# VehicleBattVMonIoT_SMD.net
KiCad netlist of a schematic drawn in EAGLE
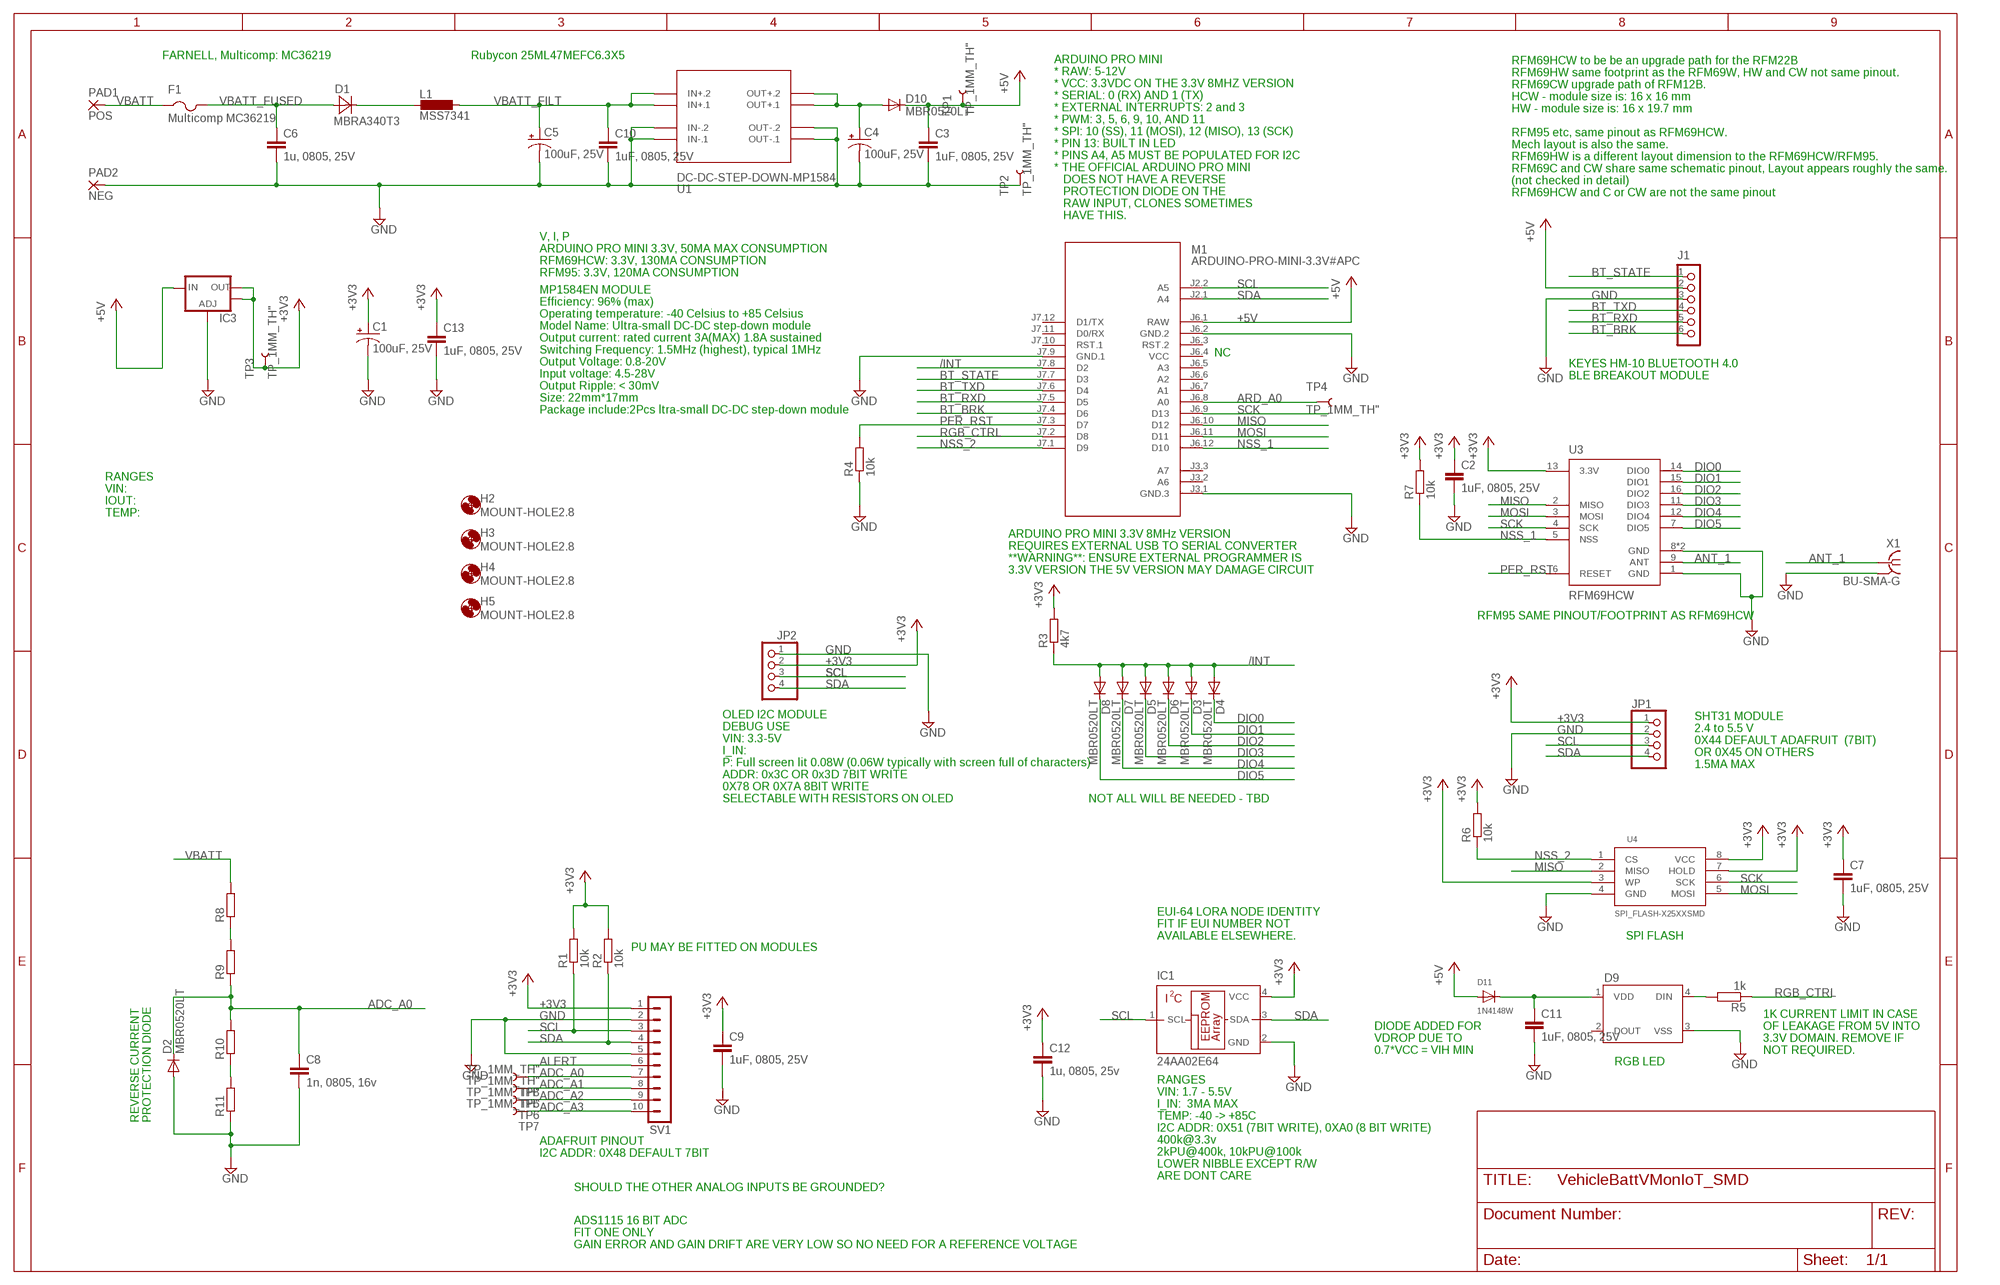
[diagram p0: schematic, sheet 1]

(export (version "E")
  (design (tool "Eeschema 10.0.6"))
  (components
    (comp (ref "C1")
      (value "100uF, 25V")
      (footprint "eagle-import:CPOL-RADIAL-100UF-25V")
      (libsource (lib "eagle-import") (part "CAP_POLPTH1"))
    )
    (comp (ref "C2")
      (value "1uF, 0805, 25V")
      (footprint "eagle-import:C0805")
      (libsource (lib "eagle-import") (part "C-EUC0805"))
    )
    (comp (ref "C3")
      (value "1uF, 0805, 25V")
      (footprint "eagle-import:C0805")
      (libsource (lib "eagle-import") (part "C-EUC0805"))
    )
    (comp (ref "C4")
      (value "100uF, 25V")
      (footprint "eagle-import:CPOL-RADIAL-100UF-25V")
      (libsource (lib "eagle-import") (part "CAP_POLPTH1"))
    )
    (comp (ref "C5")
      (value "100uF, 25V")
      (footprint "eagle-import:CPOL-RADIAL-100UF-25V")
      (libsource (lib "eagle-import") (part "CAP_POLPTH1"))
    )
    (comp (ref "C6")
      (value "1u, 0805, 25V")
      (footprint "eagle-import:C0805")
      (libsource (lib "eagle-import") (part "C-EUC0805"))
    )
    (comp (ref "C7")
      (value "1uF, 0805, 25V")
      (footprint "eagle-import:C0805")
      (libsource (lib "eagle-import") (part "C-EUC0805"))
    )
    (comp (ref "C8")
      (value "1n, 0805, 16v")
      (footprint "eagle-import:C0805")
      (libsource (lib "eagle-import") (part "C-EUC0805"))
    )
    (comp (ref "C9")
      (value "1uF, 0805, 25V")
      (footprint "eagle-import:C0805")
      (libsource (lib "eagle-import") (part "C-EUC0805"))
    )
    (comp (ref "C10")
      (value "1uF, 0805, 25V")
      (footprint "eagle-import:C0805")
      (libsource (lib "eagle-import") (part "C-EUC0805"))
    )
    (comp (ref "C11")
      (value "1uF, 0805, 25V")
      (footprint "eagle-import:C0805")
      (libsource (lib "eagle-import") (part "C-EUC0805"))
    )
    (comp (ref "C12")
      (value "1u, 0805, 25v")
      (footprint "eagle-import:C0805")
      (libsource (lib "eagle-import") (part "C-EUC0805"))
    )
    (comp (ref "C13")
      (value "1uF, 0805, 25V")
      (footprint "eagle-import:C0805")
      (libsource (lib "eagle-import") (part "C-EUC0805"))
    )
    (comp (ref "D1")
      (value "MBRA340T3")
      (footprint "eagle-import:SMA")
      (libsource (lib "eagle-import") (part "MBRA340T3"))
    )
    (comp (ref "D2")
      (value "MBR0520LT")
      (footprint "eagle-import:SOD123")
      (libsource (lib "eagle-import") (part "MBR0520LT"))
    )
    (comp (ref "D3")
      (value "MBR0520LT")
      (footprint "eagle-import:SOD123")
      (libsource (lib "eagle-import") (part "MBR0520LT"))
    )
    (comp (ref "D4")
      (value "MBR0520LT")
      (footprint "eagle-import:SOD123")
      (libsource (lib "eagle-import") (part "MBR0520LT"))
    )
    (comp (ref "D5")
      (value "MBR0520LT")
      (footprint "eagle-import:SOD123")
      (libsource (lib "eagle-import") (part "MBR0520LT"))
    )
    (comp (ref "D6")
      (value "MBR0520LT")
      (footprint "eagle-import:SOD123")
      (libsource (lib "eagle-import") (part "MBR0520LT"))
    )
    (comp (ref "D7")
      (value "MBR0520LT")
      (footprint "eagle-import:SOD123")
      (libsource (lib "eagle-import") (part "MBR0520LT"))
    )
    (comp (ref "D8")
      (value "MBR0520LT")
      (footprint "eagle-import:SOD123")
      (libsource (lib "eagle-import") (part "MBR0520LT"))
    )
    (comp (ref "D9")
      (value "WS2812B")
      (footprint "eagle-import:WS2812B")
      (libsource (lib "eagle-import") (part "WS2812B"))
    )
    (comp (ref "D10")
      (value "MBR0520LT")
      (footprint "eagle-import:SOD123")
      (libsource (lib "eagle-import") (part "MBR0520LT"))
    )
    (comp (ref "D11")
      (value "1N4148W")
      (footprint "eagle-import:SOD-323F")
      (libsource (lib "eagle-import") (part "DIODESOD-323F"))
    )
    (comp (ref "F1")
      (value "Multicomp MC36219")
      (footprint "eagle-import:1812")
      (libsource (lib "eagle-import") (part "PTCFUSE-1812"))
    )
    (comp (ref "H2")
      (value "MOUNT-HOLE2.8")
      (footprint "eagle-import:2,8")
      (libsource (lib "eagle-import") (part "MOUNT-HOLE2.8"))
    )
    (comp (ref "H3")
      (value "MOUNT-HOLE2.8")
      (footprint "eagle-import:2,8")
      (libsource (lib "eagle-import") (part "MOUNT-HOLE2.8"))
    )
    (comp (ref "H4")
      (value "MOUNT-HOLE2.8")
      (footprint "eagle-import:2,8")
      (libsource (lib "eagle-import") (part "MOUNT-HOLE2.8"))
    )
    (comp (ref "H5")
      (value "MOUNT-HOLE2.8")
      (footprint "eagle-import:2,8")
      (libsource (lib "eagle-import") (part "MOUNT-HOLE2.8"))
    )
    (comp (ref "IC1")
      (value "24AA02E64")
      (footprint "eagle-import:SOT23-5L")
      (fields (field (name "MF") "MICROCHIP") (field (name "MPN") "24AA00T-I/OTG"))
      (libsource (lib "eagle-import") (part "2400OTAA"))
    )
    (comp (ref "IC3")
      (value "V_REG_LM1117SOT223")
      (footprint "eagle-import:SOT223")
      (libsource (lib "eagle-import") (part "V_REG_LM1117SOT223"))
    )
    (comp (ref "J1")
      (value "CON_HEADER_1X06-SMD-RIGHT-ANGLED")
      (footprint "eagle-import:M1X6_MALE_RIGHT_ANGLED_SMD")
      (libsource (lib "eagle-import") (part "CON_HEADER_1X06-SMD-RIGHT-ANGLED"))
    )
    (comp (ref "JP1")
      (value "PINHD-1X4")
      (footprint "eagle-import:1X04")
      (libsource (lib "eagle-import") (part "PINHD-1X4"))
    )
    (comp (ref "JP2")
      (value "PINHD-1X4")
      (footprint "eagle-import:1X04")
      (libsource (lib "eagle-import") (part "PINHD-1X4"))
    )
    (comp (ref "L1")
      (value "MSS7341")
      (footprint "eagle-import:MSS7341")
      (libsource (lib "eagle-import") (part "MSS7341"))
    )
    (comp (ref "M1")
      (value "ARDUINO-PRO-MINI-3.3V#APC")
      (footprint "eagle-import:ARDUINO-PRO-MINI#APC")
      (libsource (lib "eagle-import") (part "ARDUINO-PRO-MINI-#APC3.3V"))
    )
    (comp (ref "PAD1")
      (value "POS")
      (footprint "eagle-import:3,81_1,4")
      (libsource (lib "eagle-import") (part "3,81/1,4"))
    )
    (comp (ref "PAD2")
      (value "NEG")
      (footprint "eagle-import:3,81_1,4")
      (libsource (lib "eagle-import") (part "3,81/1,4"))
    )
    (comp (ref "R1")
      (value "10k")
      (footprint "eagle-import:R0805")
      (libsource (lib "eagle-import") (part "R-EU_R0805"))
    )
    (comp (ref "R2")
      (value "10k")
      (footprint "eagle-import:R0805")
      (libsource (lib "eagle-import") (part "R-EU_R0805"))
    )
    (comp (ref "R3")
      (value "4k7")
      (footprint "eagle-import:R0805")
      (libsource (lib "eagle-import") (part "R-EU_R0805"))
    )
    (comp (ref "R4")
      (value "10k")
      (footprint "eagle-import:R0805")
      (libsource (lib "eagle-import") (part "R-EU_R0805"))
    )
    (comp (ref "R5")
      (value "1k")
      (footprint "eagle-import:R0805")
      (libsource (lib "eagle-import") (part "R-EU_R0805"))
    )
    (comp (ref "R6")
      (value "10k")
      (footprint "eagle-import:R0805")
      (libsource (lib "eagle-import") (part "R-EU_R0805"))
    )
    (comp (ref "R7")
      (value "10k")
      (footprint "eagle-import:R0805")
      (libsource (lib "eagle-import") (part "R-EU_R0805"))
    )
    (comp (ref "R8")
      (value "R-EU_R0805")
      (footprint "eagle-import:R0805")
      (libsource (lib "eagle-import") (part "R-EU_R0805"))
    )
    (comp (ref "R9")
      (value "R-EU_R0805")
      (footprint "eagle-import:R0805")
      (libsource (lib "eagle-import") (part "R-EU_R0805"))
    )
    (comp (ref "R10")
      (value "R-EU_R0805")
      (footprint "eagle-import:R0805")
      (libsource (lib "eagle-import") (part "R-EU_R0805"))
    )
    (comp (ref "R11")
      (value "R-EU_R0805")
      (footprint "eagle-import:R0805")
      (libsource (lib "eagle-import") (part "R-EU_R0805"))
    )
    (comp (ref "SV1")
      (value "MA10-1W")
      (footprint "eagle-import:MA10-1W")
      (libsource (lib "eagle-import") (part "MA10-1W"))
    )
    (comp (ref "TP1")
      (value "TP_1MM_TH\"")
      (footprint "eagle-import:TP_1MM_TH")
      (libsource (lib "eagle-import") (part "TP_1MM_TH{dblquote}"))
    )
    (comp (ref "TP2")
      (value "TP_1MM_TH\"")
      (footprint "eagle-import:TP_1MM_TH")
      (libsource (lib "eagle-import") (part "TP_1MM_TH{dblquote}"))
    )
    (comp (ref "TP3")
      (value "TP_1MM_TH\"")
      (footprint "eagle-import:TP_1MM_TH")
      (libsource (lib "eagle-import") (part "TP_1MM_TH{dblquote}"))
    )
    (comp (ref "TP4")
      (value "TP_1MM_TH\"")
      (footprint "eagle-import:TP_1MM_TH")
      (libsource (lib "eagle-import") (part "TP_1MM_TH{dblquote}"))
    )
    (comp (ref "TP5")
      (value "TP_1MM_TH\"")
      (footprint "eagle-import:TP_1MM_TH")
      (libsource (lib "eagle-import") (part "TP_1MM_TH{dblquote}"))
    )
    (comp (ref "TP6")
      (value "TP_1MM_TH\"")
      (footprint "eagle-import:TP_1MM_TH")
      (libsource (lib "eagle-import") (part "TP_1MM_TH{dblquote}"))
    )
    (comp (ref "TP7")
      (value "TP_1MM_TH\"")
      (footprint "eagle-import:TP_1MM_TH")
      (libsource (lib "eagle-import") (part "TP_1MM_TH{dblquote}"))
    )
    (comp (ref "TP8")
      (value "TP_1MM_TH\"")
      (footprint "eagle-import:TP_1MM_TH")
      (libsource (lib "eagle-import") (part "TP_1MM_TH{dblquote}"))
    )
    (comp (ref "U1")
      (value "DC-DC-STEP-DOWN-MP1584")
      (footprint "eagle-import:DC-DC-STEP-DOWN-MP1584")
      (libsource (lib "eagle-import") (part "DC-DC-STEP-DOWN-MP1584"))
    )
    (comp (ref "U3")
      (value "RFM69HCW")
      (footprint "eagle-import:RFM69HCW-XXXS2")
      (libsource (lib "eagle-import") (part "RFM69HCW"))
    )
    (comp (ref "U4")
      (value "SPI_FLASH-X25XXSMD")
      (footprint "eagle-import:SO08")
      (libsource (lib "eagle-import") (part "SPI_FLASH-X25XXSMD"))
    )
    (comp (ref "X1")
      (value "BU-SMA-G")
      (footprint "eagle-import:BU-SMA-G")
      (libsource (lib "eagle-import") (part "BU-SMA-G"))
    )
  )
  (nets
    (net (code "1") (name "+3V3") (class "Default")
      (node (ref "C1") (pin "1") (pinfunction "+_1") (pintype "passive"))
      (node (ref "C12") (pin "1") (pinfunction "1_1") (pintype "passive"))
      (node (ref "C13") (pin "1") (pinfunction "1_1") (pintype "passive"))
      (node (ref "C2") (pin "1") (pinfunction "1_1") (pintype "passive"))
      (node (ref "C7") (pin "1") (pinfunction "1_1") (pintype "passive"))
      (node (ref "C9") (pin "1") (pinfunction "1_1") (pintype "passive"))
      (node (ref "IC1") (pin "4") (pinfunction "VCC_4") (pintype "power_in"))
      (node (ref "IC3") (pin "2") (pinfunction "OUT_2") (pintype "output"))
      (node (ref "IC3") (pin "4") (pinfunction "OUT_4") (pintype "output"))
      (node (ref "JP1") (pin "1") (pinfunction "1_1") (pintype "passive"))
      (node (ref "JP2") (pin "2") (pinfunction "2_2") (pintype "passive"))
      (node (ref "R1") (pin "2") (pinfunction "2_2") (pintype "passive"))
      (node (ref "R2") (pin "2") (pinfunction "2_2") (pintype "passive"))
      (node (ref "R3") (pin "2") (pinfunction "2_2") (pintype "passive"))
      (node (ref "R6") (pin "2") (pinfunction "2_2") (pintype "passive"))
      (node (ref "R7") (pin "2") (pinfunction "2_2") (pintype "passive"))
      (node (ref "SV1") (pin "1") (pinfunction "1_1") (pintype "passive"))
      (node (ref "TP3") (pin "P$1") (pinfunction "1_P$1") (pintype "bidirectional"))
      (node (ref "U3") (pin "13") (pinfunction "3.3V_13") (pintype "power_in"))
      (node (ref "U4") (pin "3") (pinfunction "WP_3") (pintype "bidirectional"))
      (node (ref "U4") (pin "7") (pinfunction "HOLD_7") (pintype "bidirectional"))
      (node (ref "U4") (pin "8") (pinfunction "VCC_8") (pintype "bidirectional"))
    )
    (net (code "2") (name "+5V") (class "Default")
      (node (ref "C3") (pin "1") (pinfunction "1_1") (pintype "passive"))
      (node (ref "D10") (pin "C") (pinfunction "C_C") (pintype "passive"))
      (node (ref "D11") (pin "A") (pinfunction "A_A") (pintype "passive"))
      (node (ref "IC3") (pin "3") (pinfunction "IN_3") (pintype "input"))
      (node (ref "J1") (pin "2") (pinfunction "2_2") (pintype "bidirectional"))
      (node (ref "M1") (pin "J6.1") (pinfunction "RAW_J6.1") (pintype "power_in"))
      (node (ref "TP1") (pin "P$1") (pinfunction "1_P$1") (pintype "bidirectional"))
    )
    (net (code "3") (name "/ADC_A0") (class "Default")
      (node (ref "C8") (pin "1") (pinfunction "1_1") (pintype "passive"))
      (node (ref "D2") (pin "C") (pinfunction "C_C") (pintype "passive"))
      (node (ref "R10") (pin "2") (pinfunction "2_2") (pintype "passive"))
      (node (ref "R9") (pin "1") (pinfunction "1_1") (pintype "passive"))
      (node (ref "SV1") (pin "7") (pinfunction "7_7") (pintype "passive"))
      (node (ref "TP8") (pin "P$1") (pinfunction "1_P$1") (pintype "bidirectional"))
    )
    (net (code "4") (name "/ADC_A1") (class "Default")
      (node (ref "SV1") (pin "8") (pinfunction "8_8") (pintype "passive"))
      (node (ref "TP5") (pin "P$1") (pinfunction "1_P$1") (pintype "bidirectional"))
    )
    (net (code "5") (name "/ADC_A2") (class "Default")
      (node (ref "SV1") (pin "9") (pinfunction "9_9") (pintype "passive"))
      (node (ref "TP6") (pin "P$1") (pinfunction "1_P$1") (pintype "bidirectional"))
    )
    (net (code "6") (name "/ADC_A3") (class "Default")
      (node (ref "SV1") (pin "10") (pinfunction "10_10") (pintype "passive"))
      (node (ref "TP7") (pin "P$1") (pinfunction "1_P$1") (pintype "bidirectional"))
    )
    (net (code "7") (name "/ALERT") (class "Default")
      (node (ref "SV1") (pin "6") (pinfunction "6_6") (pintype "passive"))
    )
    (net (code "8") (name "/ANT_1") (class "Default")
      (node (ref "U3") (pin "9") (pinfunction "ANT_9") (pintype "passive"))
      (node (ref "X1") (pin "1") (pinfunction "1_1") (pintype "passive"))
    )
    (net (code "9") (name "/ARD_A0") (class "Default")
      (node (ref "M1") (pin "J6.8") (pinfunction "A0_J6.8") (pintype "bidirectional"))
      (node (ref "TP4") (pin "P$1") (pinfunction "1_P$1") (pintype "bidirectional"))
    )
    (net (code "10") (name "/BT_BRK") (class "Default")
      (node (ref "J1") (pin "6") (pinfunction "6_6") (pintype "passive"))
      (node (ref "M1") (pin "J7.4") (pinfunction "D6_J7.4") (pintype "bidirectional"))
    )
    (net (code "11") (name "/BT_RXD") (class "Default")
      (node (ref "J1") (pin "5") (pinfunction "5_5") (pintype "passive"))
      (node (ref "M1") (pin "J7.5") (pinfunction "D5_J7.5") (pintype "bidirectional"))
    )
    (net (code "12") (name "/BT_STATE") (class "Default")
      (node (ref "J1") (pin "1") (pinfunction "1_1") (pintype "bidirectional"))
      (node (ref "M1") (pin "J7.7") (pinfunction "D3_J7.7") (pintype "bidirectional"))
    )
    (net (code "13") (name "/BT_TXD") (class "Default")
      (node (ref "J1") (pin "4") (pinfunction "4_4") (pintype "passive"))
      (node (ref "M1") (pin "J7.6") (pinfunction "D4_J7.6") (pintype "bidirectional"))
    )
    (net (code "14") (name "/DIO0") (class "Default")
      (node (ref "D4") (pin "C") (pinfunction "C_C") (pintype "passive"))
      (node (ref "U3") (pin "14") (pinfunction "DIO0_14") (pintype "bidirectional"))
    )
    (net (code "15") (name "/DIO1") (class "Default")
      (node (ref "D3") (pin "C") (pinfunction "C_C") (pintype "passive"))
      (node (ref "U3") (pin "15") (pinfunction "DIO1_15") (pintype "bidirectional"))
    )
    (net (code "16") (name "/DIO2") (class "Default")
      (node (ref "D6") (pin "C") (pinfunction "C_C") (pintype "passive"))
      (node (ref "U3") (pin "16") (pinfunction "DIO2_16") (pintype "bidirectional"))
    )
    (net (code "17") (name "/DIO3") (class "Default")
      (node (ref "D5") (pin "C") (pinfunction "C_C") (pintype "passive"))
      (node (ref "U3") (pin "11") (pinfunction "DIO3_11") (pintype "bidirectional"))
    )
    (net (code "18") (name "/DIO4") (class "Default")
      (node (ref "D7") (pin "C") (pinfunction "C_C") (pintype "passive"))
      (node (ref "U3") (pin "12") (pinfunction "DIO4_12") (pintype "bidirectional"))
    )
    (net (code "19") (name "/DIO5") (class "Default")
      (node (ref "D8") (pin "C") (pinfunction "C_C") (pintype "passive"))
      (node (ref "U3") (pin "7") (pinfunction "DIO5_7") (pintype "bidirectional"))
    )
    (net (code "20") (name "/MISO") (class "Default")
      (node (ref "M1") (pin "J6.10") (pinfunction "D12_J6.10") (pintype "bidirectional"))
      (node (ref "U3") (pin "2") (pinfunction "MISO_2") (pintype "bidirectional"))
      (node (ref "U4") (pin "2") (pinfunction "MISO_2") (pintype "bidirectional"))
    )
    (net (code "21") (name "/MOSI") (class "Default")
      (node (ref "M1") (pin "J6.11") (pinfunction "D11_J6.11") (pintype "bidirectional"))
      (node (ref "U3") (pin "3") (pinfunction "MOSI_3") (pintype "input"))
      (node (ref "U4") (pin "5") (pinfunction "MOSI_5") (pintype "bidirectional"))
    )
    (net (code "22") (name "/NSS_1") (class "Default")
      (node (ref "M1") (pin "J6.12") (pinfunction "D10_J6.12") (pintype "bidirectional"))
      (node (ref "R7") (pin "1") (pinfunction "1_1") (pintype "passive"))
      (node (ref "U3") (pin "5") (pinfunction "NSS_5") (pintype "input"))
    )
    (net (code "23") (name "/NSS_2") (class "Default")
      (node (ref "M1") (pin "J7.1") (pinfunction "D9_J7.1") (pintype "bidirectional"))
      (node (ref "R6") (pin "1") (pinfunction "1_1") (pintype "passive"))
      (node (ref "U4") (pin "1") (pinfunction "CS_1") (pintype "bidirectional"))
    )
    (net (code "24") (name "/PER_RST") (class "Default")
      (node (ref "M1") (pin "J7.3") (pinfunction "D7_J7.3") (pintype "bidirectional"))
      (node (ref "R4") (pin "2") (pinfunction "2_2") (pintype "passive"))
      (node (ref "U3") (pin "6") (pinfunction "RESET_6") (pintype "input"))
    )
    (net (code "25") (name "/RGB_CTRL") (class "Default")
      (node (ref "M1") (pin "J7.2") (pinfunction "D8_J7.2") (pintype "bidirectional"))
      (node (ref "R5") (pin "1") (pinfunction "1_1") (pintype "passive"))
    )
    (net (code "26") (name "/SCK") (class "Default")
      (node (ref "M1") (pin "J6.9") (pinfunction "D13_J6.9") (pintype "bidirectional"))
      (node (ref "U3") (pin "4") (pinfunction "SCK_4") (pintype "input"))
      (node (ref "U4") (pin "6") (pinfunction "SCK_6") (pintype "bidirectional"))
    )
    (net (code "27") (name "/SCL") (class "Default")
      (node (ref "IC1") (pin "1") (pinfunction "SCL_1") (pintype "input"))
      (node (ref "JP1") (pin "3") (pinfunction "3_3") (pintype "passive"))
      (node (ref "JP2") (pin "3") (pinfunction "3_3") (pintype "passive"))
      (node (ref "M1") (pin "J2.2") (pinfunction "A5_J2.2") (pintype "bidirectional"))
      (node (ref "R1") (pin "1") (pinfunction "1_1") (pintype "passive"))
      (node (ref "SV1") (pin "3") (pinfunction "3_3") (pintype "passive"))
    )
    (net (code "28") (name "/SDA") (class "Default")
      (node (ref "IC1") (pin "3") (pinfunction "SDA_3") (pintype "bidirectional"))
      (node (ref "JP1") (pin "4") (pinfunction "4_4") (pintype "passive"))
      (node (ref "JP2") (pin "4") (pinfunction "4_4") (pintype "passive"))
      (node (ref "M1") (pin "J2.1") (pinfunction "A4_J2.1") (pintype "bidirectional"))
      (node (ref "R2") (pin "1") (pinfunction "1_1") (pintype "passive"))
      (node (ref "SV1") (pin "4") (pinfunction "4_4") (pintype "passive"))
    )
    (net (code "29") (name "/VBATT") (class "Default")
      (node (ref "F1") (pin "1") (pinfunction "1_1") (pintype "passive"))
      (node (ref "PAD1") (pin "1") (pinfunction "P_1") (pintype "passive"))
      (node (ref "R8") (pin "2") (pinfunction "2_2") (pintype "passive"))
    )
    (net (code "30") (name "/VBATT_FILT") (class "Default")
      (node (ref "C10") (pin "1") (pinfunction "1_1") (pintype "passive"))
      (node (ref "C5") (pin "1") (pinfunction "+_1") (pintype "passive"))
      (node (ref "L1") (pin "2") (pinfunction "2_2") (pintype "passive"))
      (node (ref "U1") (pin "IN+.1") (pinfunction "IN+.1_IN+.1") (pintype "bidirectional"))
      (node (ref "U1") (pin "IN+.2") (pinfunction "IN+.2_IN+.2") (pintype "bidirectional"))
    )
    (net (code "31") (name "/VBATT_FUSED") (class "Default")
      (node (ref "C6") (pin "1") (pinfunction "1_1") (pintype "passive"))
      (node (ref "D1") (pin "A") (pinfunction "A_A") (pintype "passive"))
      (node (ref "F1") (pin "2") (pinfunction "2_2") (pintype "passive"))
    )
    (net (code "32") (name "/VCC") (class "Default")
      (node (ref "M1") (pin "J6.4") (pinfunction "VCC_J6.4") (pintype "power_in"))
    )
    (net (code "33") (name "/{slash}INT") (class "Default")
      (node (ref "D3") (pin "A") (pinfunction "A_A") (pintype "passive"))
      (node (ref "D4") (pin "A") (pinfunction "A_A") (pintype "passive"))
      (node (ref "D5") (pin "A") (pinfunction "A_A") (pintype "passive"))
      (node (ref "D6") (pin "A") (pinfunction "A_A") (pintype "passive"))
      (node (ref "D7") (pin "A") (pinfunction "A_A") (pintype "passive"))
      (node (ref "D8") (pin "A") (pinfunction "A_A") (pintype "passive"))
      (node (ref "M1") (pin "J7.8") (pinfunction "D2_J7.8") (pintype "bidirectional"))
      (node (ref "R3") (pin "1") (pinfunction "1_1") (pintype "passive"))
    )
    (net (code "34") (name "GND") (class "Default")
      (node (ref "C1") (pin "2") (pinfunction "-_2") (pintype "passive"))
      (node (ref "C10") (pin "2") (pinfunction "2_2") (pintype "passive"))
      (node (ref "C11") (pin "2") (pinfunction "2_2") (pintype "passive"))
      (node (ref "C12") (pin "2") (pinfunction "2_2") (pintype "passive"))
      (node (ref "C13") (pin "2") (pinfunction "2_2") (pintype "passive"))
      (node (ref "C2") (pin "2") (pinfunction "2_2") (pintype "passive"))
      (node (ref "C3") (pin "2") (pinfunction "2_2") (pintype "passive"))
      (node (ref "C4") (pin "2") (pinfunction "-_2") (pintype "passive"))
      (node (ref "C5") (pin "2") (pinfunction "-_2") (pintype "passive"))
      (node (ref "C6") (pin "2") (pinfunction "2_2") (pintype "passive"))
      (node (ref "C7") (pin "2") (pinfunction "2_2") (pintype "passive"))
      (node (ref "C8") (pin "2") (pinfunction "2_2") (pintype "passive"))
      (node (ref "C9") (pin "2") (pinfunction "2_2") (pintype "passive"))
      (node (ref "D2") (pin "A") (pinfunction "A_A") (pintype "passive"))
      (node (ref "D9") (pin "3") (pinfunction "VSS_3") (pintype "power_in"))
      (node (ref "IC1") (pin "2") (pinfunction "GND_2") (pintype "power_in"))
      (node (ref "IC3") (pin "1") (pinfunction "ADJ_1") (pintype "input"))
      (node (ref "J1") (pin "3") (pinfunction "3_3") (pintype "passive"))
      (node (ref "JP1") (pin "2") (pinfunction "2_2") (pintype "passive"))
      (node (ref "JP2") (pin "1") (pinfunction "1_1") (pintype "passive"))
      (node (ref "M1") (pin "J3.1") (pinfunction "GND.3_J3.1") (pintype "bidirectional"))
      (node (ref "M1") (pin "J6.2") (pinfunction "GND.2_J6.2") (pintype "power_in"))
      (node (ref "M1") (pin "J7.9") (pinfunction "GND.1_J7.9") (pintype "power_in"))
      (node (ref "PAD2") (pin "1") (pinfunction "P_1") (pintype "passive"))
      (node (ref "R11") (pin "1") (pinfunction "1_1") (pintype "passive"))
      (node (ref "R4") (pin "1") (pinfunction "1_1") (pintype "passive"))
      (node (ref "SV1") (pin "2") (pinfunction "2_2") (pintype "passive"))
      (node (ref "SV1") (pin "5") (pinfunction "5_5") (pintype "passive"))
      (node (ref "TP2") (pin "P$1") (pinfunction "1_P$1") (pintype "bidirectional"))
      (node (ref "U1") (pin "IN-.1") (pinfunction "IN-.1_IN-.1") (pintype "bidirectional"))
      (node (ref "U1") (pin "IN-.2") (pinfunction "IN-.2_IN-.2") (pintype "bidirectional"))
      (node (ref "U1") (pin "OUT-.1") (pinfunction "OUT-.1_OUT-.1") (pintype "bidirectional"))
      (node (ref "U1") (pin "OUT-.2") (pinfunction "OUT-.2_OUT-.2") (pintype "bidirectional"))
      (node (ref "U3") (pin "1") (pinfunction "GND_1") (pintype "power_in"))
      (node (ref "U3") (pin "10") (pinfunction "GND_10") (pintype "power_in"))
      (node (ref "U3") (pin "8") (pinfunction "GND_8") (pintype "power_in"))
      (node (ref "U4") (pin "4") (pinfunction "GND_4") (pintype "bidirectional"))
      (node (ref "X1") (pin "2") (pinfunction "2_2") (pintype "passive"))
      (node (ref "X1") (pin "3") (pinfunction "2_3") (pintype "passive"))
      (node (ref "X1") (pin "4") (pinfunction "2_4") (pintype "passive"))
      (node (ref "X1") (pin "5") (pinfunction "2_5") (pintype "passive"))
    )
    (net (code "35") (name "Net-(C4-+)") (class "Default")
      (node (ref "C4") (pin "1") (pinfunction "+_1") (pintype "passive"))
      (node (ref "D10") (pin "A") (pinfunction "A_A") (pintype "passive"))
      (node (ref "U1") (pin "OUT+.1") (pinfunction "OUT+.1_OUT+.1") (pintype "bidirectional"))
      (node (ref "U1") (pin "OUT+.2") (pinfunction "OUT+.2_OUT+.2") (pintype "bidirectional"))
    )
    (net (code "36") (name "Net-(D1-PadC)") (class "Default")
      (node (ref "D1") (pin "C") (pinfunction "C_C") (pintype "passive"))
      (node (ref "L1") (pin "1") (pinfunction "1_1") (pintype "passive"))
    )
    (net (code "37") (name "Net-(D9-DIN)") (class "Default")
      (node (ref "D9") (pin "4") (pinfunction "DIN_4") (pintype "input"))
      (node (ref "R5") (pin "2") (pinfunction "2_2") (pintype "passive"))
    )
    (net (code "38") (name "Net-(D9-VDD)") (class "Default")
      (node (ref "C11") (pin "1") (pinfunction "1_1") (pintype "passive"))
      (node (ref "D11") (pin "C") (pinfunction "C_C") (pintype "passive"))
      (node (ref "D9") (pin "1") (pinfunction "VDD_1") (pintype "power_in"))
    )
    (net (code "39") (name "Net-(R8-Pad1)") (class "Default")
      (node (ref "R8") (pin "1") (pinfunction "1_1") (pintype "passive"))
      (node (ref "R9") (pin "2") (pinfunction "2_2") (pintype "passive"))
    )
    (net (code "40") (name "Net-(R10-Pad1)") (class "Default")
      (node (ref "R10") (pin "1") (pinfunction "1_1") (pintype "passive"))
      (node (ref "R11") (pin "2") (pinfunction "2_2") (pintype "passive"))
    )
    (net (code "41") (name "unconnected-(D9-DOUT-Pad2)") (class "Default")
      (node (ref "D9") (pin "2") (pinfunction "DOUT_2") (pintype "output"))
    )
    (net (code "42") (name "unconnected-(M1-A1-PadJ6.7)") (class "Default")
      (node (ref "M1") (pin "J6.7") (pinfunction "A1_J6.7") (pintype "bidirectional"))
    )
    (net (code "43") (name "unconnected-(M1-A2-PadJ6.6)") (class "Default")
      (node (ref "M1") (pin "J6.6") (pinfunction "A2_J6.6") (pintype "bidirectional"))
    )
    (net (code "44") (name "unconnected-(M1-A3-PadJ6.5)") (class "Default")
      (node (ref "M1") (pin "J6.5") (pinfunction "A3_J6.5") (pintype "bidirectional"))
    )
    (net (code "45") (name "unconnected-(M1-A6-PadJ3.2)") (class "Default")
      (node (ref "M1") (pin "J3.2") (pinfunction "A6_J3.2") (pintype "bidirectional"))
    )
    (net (code "46") (name "unconnected-(M1-A7-PadJ3.3)") (class "Default")
      (node (ref "M1") (pin "J3.3") (pinfunction "A7_J3.3") (pintype "bidirectional"))
    )
    (net (code "47") (name "unconnected-(M1-D0{slash}RX-PadJ7.11)") (class "Default")
      (node (ref "M1") (pin "J7.11") (pinfunction "D0/RX_J7.11") (pintype "bidirectional"))
    )
    (net (code "48") (name "unconnected-(M1-D1{slash}TX-PadJ7.12)") (class "Default")
      (node (ref "M1") (pin "J7.12") (pinfunction "D1/TX_J7.12") (pintype "bidirectional"))
    )
    (net (code "49") (name "unconnected-(M1-RST.1-PadJ7.10)") (class "Default")
      (node (ref "M1") (pin "J7.10") (pinfunction "RST.1_J7.10") (pintype "bidirectional"))
    )
    (net (code "50") (name "unconnected-(M1-RST.2-PadJ6.3)") (class "Default")
      (node (ref "M1") (pin "J6.3") (pinfunction "RST.2_J6.3") (pintype "bidirectional"))
    )
  )
)
